# programmer.net
KiCad netlist of a schematic drawn in EAGLE
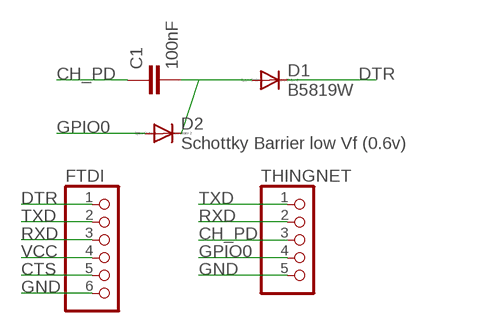
[diagram p0: schematic, sheet 1]

(export (version "E")
  (design (tool "Eeschema 10.0.6"))
  (components
    (comp (ref "C1")
      (value "100nF")
      (footprint "eagle-import:C025-024X044")
      (libsource (lib "eagle-import") (part "C-EU025-024X044"))
    )
    (comp (ref "D1")
      (value "B5819W")
      (footprint "eagle-import:D-5")
      (libsource (lib "eagle-import") (part "DIODE-D-5"))
    )
    (comp (ref "D2")
      (value "Schottky Barrier low Vf (0.6v)")
      (footprint "eagle-import:D-5")
      (libsource (lib "eagle-import") (part "DIODE-D-5"))
    )
    (comp (ref "FTDI")
      (value "PINHD-1X6")
      (footprint "eagle-import:1X06")
      (libsource (lib "eagle-import") (part "PINHD-1X6"))
    )
    (comp (ref "THINGNET")
      (value "PINHD-1X5")
      (footprint "eagle-import:1X05")
      (libsource (lib "eagle-import") (part "PINHD-1X5"))
    )
  )
  (nets
    (net (code "1") (name "/CH_PD") (class "Default")
      (node (ref "C1") (pin "1") (pinfunction "1_1") (pintype "passive"))
      (node (ref "THINGNET") (pin "3") (pinfunction "3_3") (pintype "passive"))
    )
    (net (code "2") (name "/CTS") (class "Default")
      (node (ref "FTDI") (pin "5") (pinfunction "5_5") (pintype "passive"))
    )
    (net (code "3") (name "/DTR") (class "Default")
      (node (ref "D1") (pin "C") (pinfunction "C_C") (pintype "passive"))
      (node (ref "FTDI") (pin "1") (pinfunction "1_1") (pintype "passive"))
    )
    (net (code "4") (name "/GND") (class "Default")
      (node (ref "FTDI") (pin "6") (pinfunction "6_6") (pintype "passive"))
      (node (ref "THINGNET") (pin "5") (pinfunction "5_5") (pintype "passive"))
    )
    (net (code "5") (name "/GPIO0") (class "Default")
      (node (ref "D2") (pin "A") (pinfunction "A_A") (pintype "passive"))
      (node (ref "THINGNET") (pin "4") (pinfunction "4_4") (pintype "passive"))
    )
    (net (code "6") (name "/RXD") (class "Default")
      (node (ref "FTDI") (pin "3") (pinfunction "3_3") (pintype "passive"))
      (node (ref "THINGNET") (pin "2") (pinfunction "2_2") (pintype "passive"))
    )
    (net (code "7") (name "/TXD") (class "Default")
      (node (ref "FTDI") (pin "2") (pinfunction "2_2") (pintype "passive"))
      (node (ref "THINGNET") (pin "1") (pinfunction "1_1") (pintype "passive"))
    )
    (net (code "8") (name "/VCC") (class "Default")
      (node (ref "FTDI") (pin "4") (pinfunction "4_4") (pintype "passive"))
    )
    (net (code "9") (name "Net-(C1-Pad2)") (class "Default")
      (node (ref "C1") (pin "2") (pinfunction "2_2") (pintype "passive"))
      (node (ref "D1") (pin "A") (pinfunction "A_A") (pintype "passive"))
      (node (ref "D2") (pin "C") (pinfunction "C_C") (pintype "passive"))
    )
  )
)
